# GoodNightLight.net
KiCad netlist of a schematic drawn in EAGLE
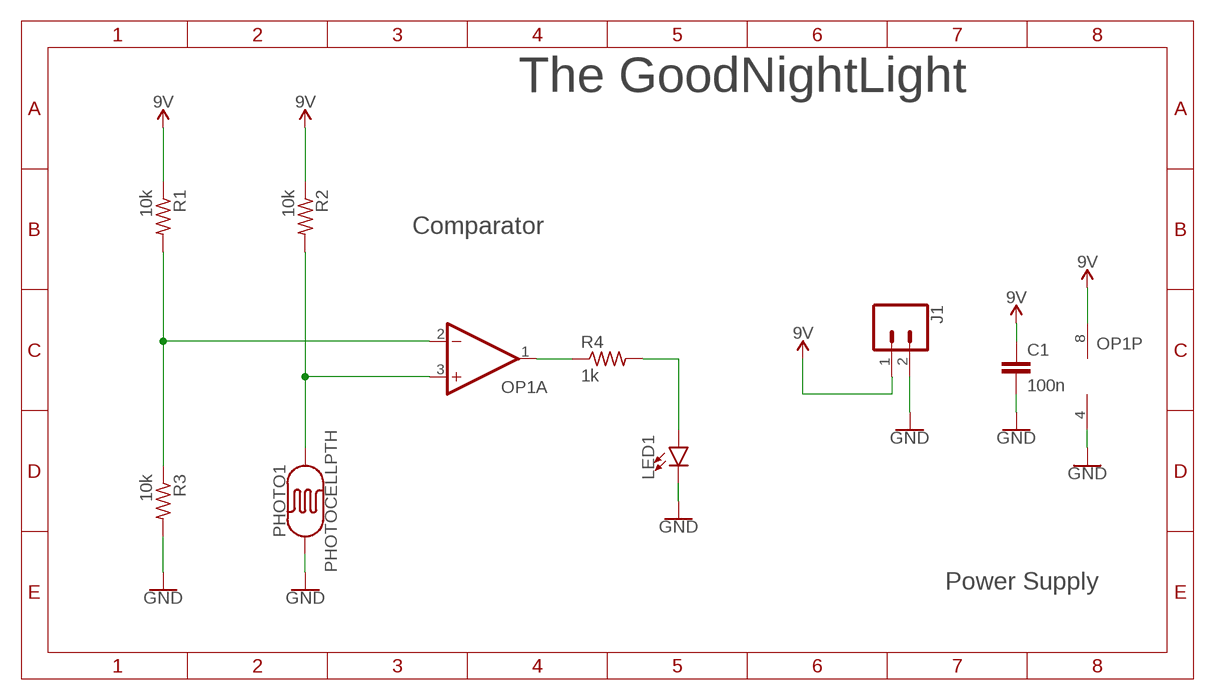
[diagram p0: schematic, sheet 1]

(export (version "E")
  (design (tool "Eeschema 10.0.6"))
  (components
    (comp (ref "C1")
      (value "100n")
      (footprint "eagle-import:C0603")
      (libsource (lib "eagle-import") (part "CAPACITOR0603"))
    )
    (comp (ref "J1")
      (value "CONN_02")
      (footprint "eagle-import:1X02")
      (libsource (lib "eagle-import") (part "CONN_02"))
    )
    (comp (ref "LED1")
      (value "LED5MM")
      (footprint "eagle-import:LED_5MM")
      (libsource (lib "eagle-import") (part "LED5MM"))
    )
    (comp (ref "OP1")
      (value "OP-DUALR")
      (footprint "eagle-import:SO8")
      (fields (field (name "MPN") "AD8607ARMZ-R2"))
      (libsource (lib "eagle-import") (part "OP-DUALR"))
    )
    (comp (ref "PHOTO1")
      (value "PHOTOCELLPTH")
      (footprint "eagle-import:PHOTOCELL")
      (libsource (lib "eagle-import") (part "PHOTOCELLPTH"))
    )
    (comp (ref "R1")
      (value "10k")
      (footprint "eagle-import:R0603")
      (libsource (lib "eagle-import") (part "RESISTOR0603"))
    )
    (comp (ref "R2")
      (value "10k")
      (footprint "eagle-import:R0603")
      (libsource (lib "eagle-import") (part "RESISTOR0603"))
    )
    (comp (ref "R3")
      (value "10k")
      (footprint "eagle-import:R0603")
      (libsource (lib "eagle-import") (part "RESISTOR0603"))
    )
    (comp (ref "R4")
      (value "1k")
      (footprint "eagle-import:R0603")
      (libsource (lib "eagle-import") (part "RESISTOR0603"))
    )
  )
  (nets
    (net (code "1") (name "9V") (class "Default")
      (node (ref "C1") (pin "1") (pinfunction "1_1") (pintype "passive"))
      (node (ref "J1") (pin "1") (pinfunction "1_1") (pintype "passive"))
      (node (ref "OP1") (pin "8") (pinfunction "V+_8") (pintype "power_in"))
      (node (ref "R1") (pin "1") (pinfunction "1_1") (pintype "passive"))
      (node (ref "R2") (pin "1") (pinfunction "1_1") (pintype "passive"))
    )
    (net (code "2") (name "GND") (class "Default")
      (node (ref "C1") (pin "2") (pinfunction "2_2") (pintype "passive"))
      (node (ref "J1") (pin "2") (pinfunction "2_2") (pintype "passive"))
      (node (ref "LED1") (pin "K") (pinfunction "C_K") (pintype "passive"))
      (node (ref "OP1") (pin "4") (pinfunction "V-_4") (pintype "power_in"))
      (node (ref "PHOTO1") (pin "1") (pinfunction "P$1_1") (pintype "bidirectional"))
      (node (ref "R3") (pin "2") (pinfunction "2_2") (pintype "passive"))
    )
    (net (code "3") (name "Net-(LED1-PadA)") (class "Default")
      (node (ref "LED1") (pin "A") (pinfunction "A_A") (pintype "passive"))
      (node (ref "R4") (pin "2") (pinfunction "2_2") (pintype "passive"))
    )
    (net (code "4") (name "Net-(OP1A-+IN)") (class "Default")
      (node (ref "OP1") (pin "3") (pinfunction "+IN_3") (pintype "input"))
      (node (ref "PHOTO1") (pin "2") (pinfunction "P$2_2") (pintype "bidirectional"))
      (node (ref "R2") (pin "2") (pinfunction "2_2") (pintype "passive"))
    )
    (net (code "5") (name "Net-(OP1A--IN)") (class "Default")
      (node (ref "OP1") (pin "2") (pinfunction "-IN_2") (pintype "input"))
      (node (ref "R1") (pin "2") (pinfunction "2_2") (pintype "passive"))
      (node (ref "R3") (pin "1") (pinfunction "1_1") (pintype "passive"))
    )
    (net (code "6") (name "Net-(OP1A-OUT)") (class "Default")
      (node (ref "OP1") (pin "1") (pinfunction "OUT_1") (pintype "output"))
      (node (ref "R4") (pin "1") (pinfunction "1_1") (pintype "passive"))
    )
  )
)
